# Input_Filter.net
KiCad netlist of a schematic drawn in Altium Designer
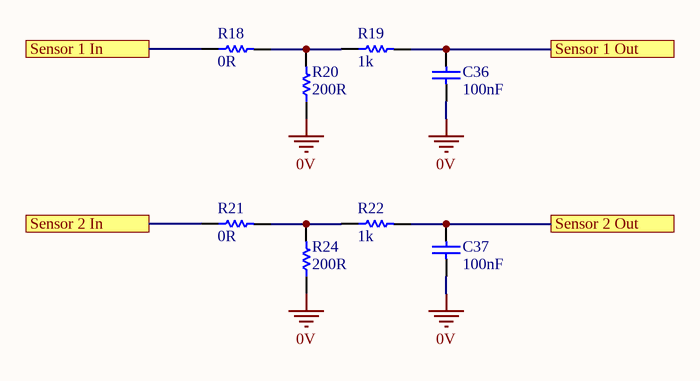
[diagram p0: Input Filter.SchDoc]

(export (version "E")
  (design (tool "Eeschema 10.0.6"))
  (components
    (comp (ref "C36")
      (value "100nF")
      (footprint "0805")
      (fields
        (field (name "PART NUMBER") "GCM21BR71E104KA37L")
        (field (name "TOLERANCE") "10%")
        (field (name "MANUFACTURER") "muRata")
      )
      (libsource (lib "ts_20-standard-library") (part "Capacitor"))
    )
    (comp (ref "C37")
      (value "100nF")
      (footprint "0805")
      (fields
        (field (name "PART NUMBER") "GCM21BR71E104KA37L")
        (field (name "TOLERANCE") "10%")
        (field (name "MANUFACTURER") "muRata")
      )
      (libsource (lib "ts_20-standard-library") (part "Capacitor"))
    )
    (comp (ref "R18")
      (value "0R")
      (footprint "0805")
      (fields
        (field (name "PART NUMBER") "RC0805FR070RL")
        (field (name "MANUFACTURER") "YAGEO")
        (field (name "TOLERANCE") "0.01")
      )
      (libsource (lib "ts_20-standard-library") (part "Resistor"))
    )
    (comp (ref "R19")
      (value "1k")
      (footprint "0805")
      (fields
        (field (name "PART NUMBER") "RC0805FR071KL")
        (field (name "MANUFACTURER") "YAGEO")
        (field (name "TOLERANCE") "0.01")
      )
      (libsource (lib "ts_20-standard-library") (part "Resistor"))
    )
    (comp (ref "R20")
      (value "200R")
      (footprint "0805")
      (fields
        (field (name "PART NUMBER") "RC0805FR07200RL")
        (field (name "MANUFACTURER") "YAGEO")
        (field (name "TOLERANCE") "0.01")
      )
      (libsource (lib "ts_20-standard-library") (part "Resistor"))
    )
    (comp (ref "R21")
      (value "0R")
      (footprint "0805")
      (fields
        (field (name "PART NUMBER") "RC0805FR070RL")
        (field (name "MANUFACTURER") "YAGEO")
        (field (name "TOLERANCE") "0.01")
      )
      (libsource (lib "ts_20-standard-library") (part "Resistor"))
    )
    (comp (ref "R22")
      (value "1k")
      (footprint "0805")
      (fields
        (field (name "PART NUMBER") "RC0805FR071KL")
        (field (name "MANUFACTURER") "YAGEO")
        (field (name "TOLERANCE") "0.01")
      )
      (libsource (lib "ts_20-standard-library") (part "Resistor"))
    )
    (comp (ref "R24")
      (value "200R")
      (footprint "0805")
      (fields
        (field (name "PART NUMBER") "RC0805FR07200RL")
        (field (name "MANUFACTURER") "YAGEO")
        (field (name "TOLERANCE") "0.01")
      )
      (libsource (lib "ts_20-standard-library") (part "Resistor"))
    )
  )
  (nets
    (net (code "1") (name "/Sensor 1 In") (class "Default")
      (node (ref "R18") (pin "1") (pinfunction "1_1") (pintype "passive"))
    )
    (net (code "2") (name "/Sensor 1 Out") (class "Default")
      (node (ref "C36") (pin "2") (pinfunction "2_2") (pintype "passive"))
      (node (ref "R19") (pin "2") (pinfunction "2_2") (pintype "passive"))
    )
    (net (code "3") (name "/Sensor 2 In") (class "Default")
      (node (ref "R21") (pin "1") (pinfunction "1_1") (pintype "passive"))
    )
    (net (code "4") (name "/Sensor 2 Out") (class "Default")
      (node (ref "C37") (pin "2") (pinfunction "2_2") (pintype "passive"))
      (node (ref "R22") (pin "2") (pinfunction "2_2") (pintype "passive"))
    )
    (net (code "5") (name "0V") (class "Default")
      (node (ref "C36") (pin "1") (pinfunction "1_1") (pintype "passive"))
      (node (ref "C37") (pin "1") (pinfunction "1_1") (pintype "passive"))
      (node (ref "R20") (pin "1") (pinfunction "1_1") (pintype "passive"))
      (node (ref "R24") (pin "1") (pinfunction "1_1") (pintype "passive"))
    )
    (net (code "6") (name "Net-(R18-Pad2)") (class "Default")
      (node (ref "R18") (pin "2") (pinfunction "2_2") (pintype "passive"))
      (node (ref "R19") (pin "1") (pinfunction "1_1") (pintype "passive"))
      (node (ref "R20") (pin "2") (pinfunction "2_2") (pintype "passive"))
    )
    (net (code "7") (name "Net-(R21-Pad2)") (class "Default")
      (node (ref "R21") (pin "2") (pinfunction "2_2") (pintype "passive"))
      (node (ref "R22") (pin "1") (pinfunction "1_1") (pintype "passive"))
      (node (ref "R24") (pin "2") (pinfunction "2_2") (pintype "passive"))
    )
  )
)
